# Peripherals.net
KiCad netlist of a schematic drawn in Altium Designer
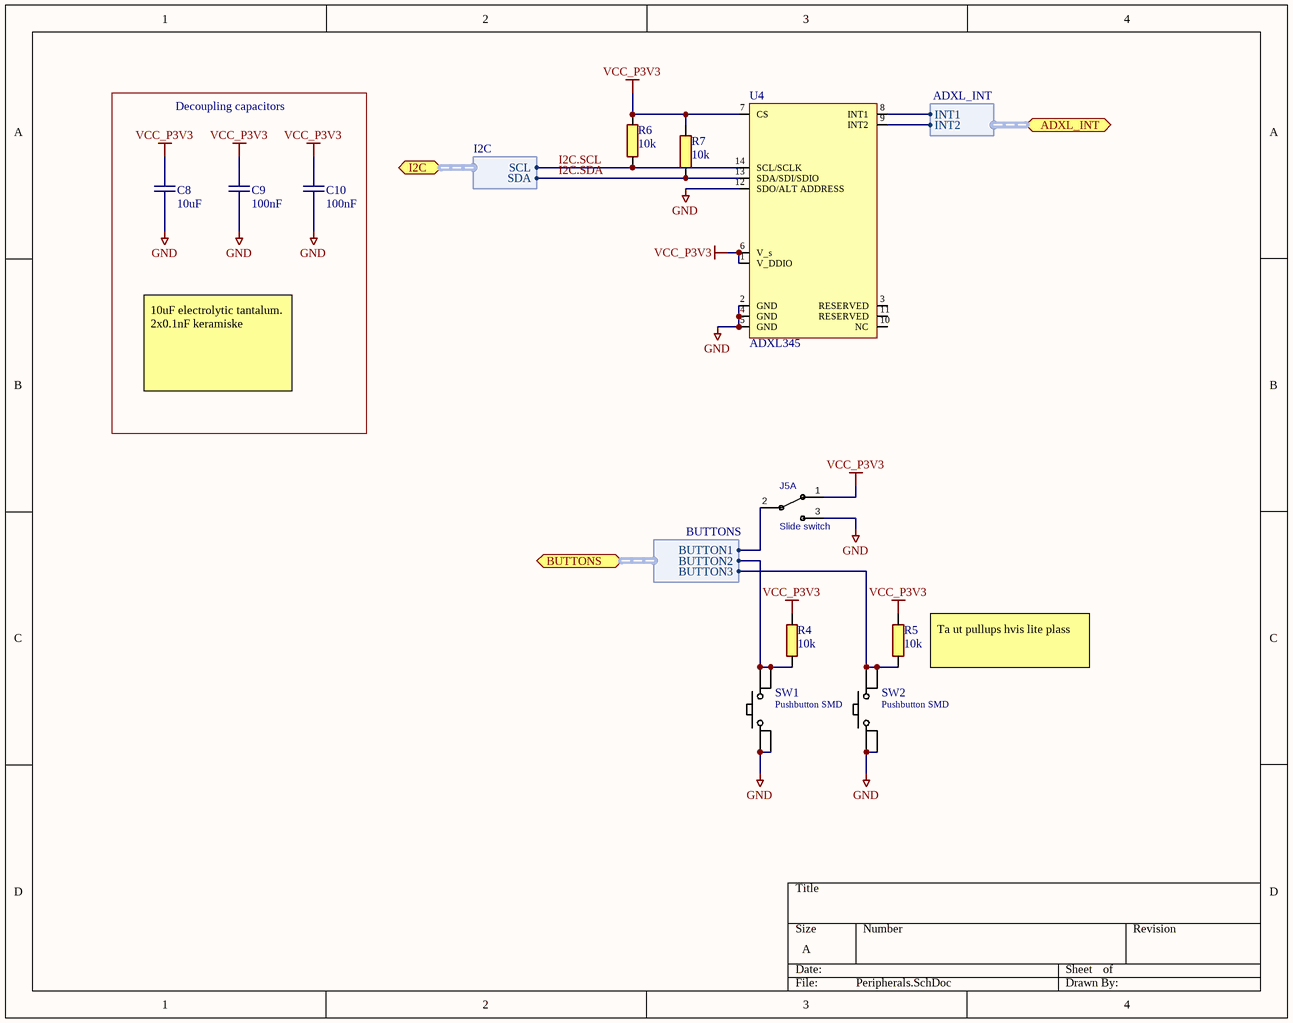
[diagram p0: Peripherals.SchDoc]

(export (version "E")
  (design (tool "Eeschema 10.0.6"))
  (components
    (comp (ref "C8")
      (value "10uF")
      (footprint "CAPC1206(3216)170_N")
      (description "X5R 50V 10%")
      (libsource (lib "OVLib") (part "CAP"))
    )
    (comp (ref "C9")
      (value "100nF")
      (footprint "CAPC0603(1608)55_N")
      (description "X7R 50V 5%")
      (libsource (lib "OVLib") (part "CAP"))
    )
    (comp (ref "C10")
      (value "100nF")
      (footprint "CAPC0603(1608)55_N")
      (description "X7R 50V 5%")
      (libsource (lib "OVLib") (part "CAP"))
    )
    (comp (ref "J5")
      (value "Slide switch")
      (footprint "OS202011MA0QS1")
      (description "Vinklet")
      (libsource (lib "OVLib") (part "Slide_switch_DPDT_RA"))
    )
    (comp (ref "R4")
      (value "10k")
      (footprint "RESC0603(1608)_N")
      (description "0.1W 1% Thick film resistor")
      (libsource (lib "OVLib") (part "Resistor2"))
    )
    (comp (ref "R5")
      (value "10k")
      (footprint "RESC0603(1608)_N")
      (description "0.1W 1% Thick film resistor")
      (libsource (lib "OVLib") (part "Resistor2"))
    )
    (comp (ref "R6")
      (value "10k")
      (footprint "RESC0603(1608)_N")
      (description "0.1W 1% Thick film resistor")
      (libsource (lib "OVLib") (part "Resistor2"))
    )
    (comp (ref "R7")
      (value "10k")
      (footprint "RESC0603(1608)_N")
      (description "0.1W 1% Thick film resistor")
      (libsource (lib "OVLib") (part "Resistor2"))
    )
    (comp (ref "SW1")
      (value "Pushbutton SMD")
      (footprint "SOIC254P500X160-4")
      (libsource (lib "OVLib") (part "Pushbutton"))
    )
    (comp (ref "SW2")
      (value "Pushbutton SMD")
      (footprint "SOIC254P500X160-4")
      (libsource (lib "OVLib") (part "Pushbutton"))
    )
    (comp (ref "U4") (value "ADXL345") (footprint "ADXL345") (libsource (lib "Schlib1") (part "ADXL345")))
  )
  (nets
    (net (code "4") (name "/BUTTON1") (class "Default")
      (node (ref "J5") (pin "2") (pinfunction "2_2") (pintype "passive"))
    )
    (net (code "5") (name "/BUTTON2") (class "Default")
      (node (ref "R4") (pin "1") (pinfunction "1_1") (pintype "passive"))
      (node (ref "SW1") (pin "3") (pinfunction "3_3") (pintype "passive"))
      (node (ref "SW1") (pin "4") (pinfunction "4_4") (pintype "passive"))
    )
    (net (code "6") (name "/BUTTON3") (class "Default")
      (node (ref "R5") (pin "1") (pinfunction "1_1") (pintype "passive"))
      (node (ref "SW2") (pin "3") (pinfunction "3_3") (pintype "passive"))
      (node (ref "SW2") (pin "4") (pinfunction "4_4") (pintype "passive"))
    )
    (net (code "7") (name "/I2C.SCL") (class "Default")
      (node (ref "R6") (pin "1") (pinfunction "1_1") (pintype "passive"))
      (node (ref "U4") (pin "14") (pinfunction "SCL/SCLK_14") (pintype "passive"))
    )
    (net (code "8") (name "/I2C.SDA") (class "Default")
      (node (ref "R7") (pin "1") (pinfunction "1_1") (pintype "passive"))
      (node (ref "U4") (pin "13") (pinfunction "SDA/SDI/SDIO_13") (pintype "passive"))
    )
    (net (code "9") (name "/INT1") (class "Default")
      (node (ref "U4") (pin "8") (pinfunction "INT1_8") (pintype "passive"))
    )
    (net (code "10") (name "/INT2") (class "Default")
      (node (ref "U4") (pin "9") (pinfunction "INT2_9") (pintype "passive"))
    )
    (net (code "14") (name "GND") (class "Default")
      (node (ref "C10") (pin "1") (pinfunction "1_1") (pintype "passive"))
      (node (ref "C8") (pin "1") (pinfunction "1_1") (pintype "passive"))
      (node (ref "C9") (pin "1") (pinfunction "1_1") (pintype "passive"))
      (node (ref "J5") (pin "3") (pinfunction "3_3") (pintype "passive"))
      (node (ref "SW1") (pin "1") (pinfunction "1_1") (pintype "passive"))
      (node (ref "SW1") (pin "2") (pinfunction "2_2") (pintype "passive"))
      (node (ref "SW2") (pin "1") (pinfunction "1_1") (pintype "passive"))
      (node (ref "SW2") (pin "2") (pinfunction "2_2") (pintype "passive"))
      (node (ref "U4") (pin "12") (pinfunction "SDO/ALT_ADDRESS_12") (pintype "passive"))
      (node (ref "U4") (pin "2") (pinfunction "GND_2") (pintype "passive"))
      (node (ref "U4") (pin "4") (pinfunction "GND_4") (pintype "passive"))
      (node (ref "U4") (pin "5") (pinfunction "GND_5") (pintype "passive"))
    )
    (net (code "15") (name "VCC_P3V3") (class "Default")
      (node (ref "C10") (pin "2") (pinfunction "2_2") (pintype "passive"))
      (node (ref "C8") (pin "2") (pinfunction "2_2") (pintype "passive"))
      (node (ref "C9") (pin "2") (pinfunction "2_2") (pintype "passive"))
      (node (ref "J5") (pin "1") (pinfunction "1_1") (pintype "passive"))
      (node (ref "R4") (pin "2") (pinfunction "2_2") (pintype "passive"))
      (node (ref "R5") (pin "2") (pinfunction "2_2") (pintype "passive"))
      (node (ref "R6") (pin "2") (pinfunction "2_2") (pintype "passive"))
      (node (ref "R7") (pin "2") (pinfunction "2_2") (pintype "passive"))
      (node (ref "U4") (pin "1") (pinfunction "V_DDIO_1") (pintype "passive"))
      (node (ref "U4") (pin "6") (pinfunction "V_s_6") (pintype "passive"))
      (node (ref "U4") (pin "7") (pinfunction "CS_7") (pintype "passive"))
    )
    (net (code "16") (name "unconnected-(U4-NC-Pad10)") (class "Default")
      (node (ref "U4") (pin "10") (pinfunction "NC_10") (pintype "passive"))
    )
    (net (code "17") (name "unconnected-(U4-RESERVED-Pad3)") (class "Default")
      (node (ref "U4") (pin "3") (pinfunction "RESERVED_3") (pintype "passive"))
    )
    (net (code "18") (name "unconnected-(U4-RESERVED-Pad11)") (class "Default")
      (node (ref "U4") (pin "11") (pinfunction "RESERVED_11") (pintype "passive"))
    )
  )
)
